# byteworker.net
KiCad netlist of a schematic drawn in EAGLE
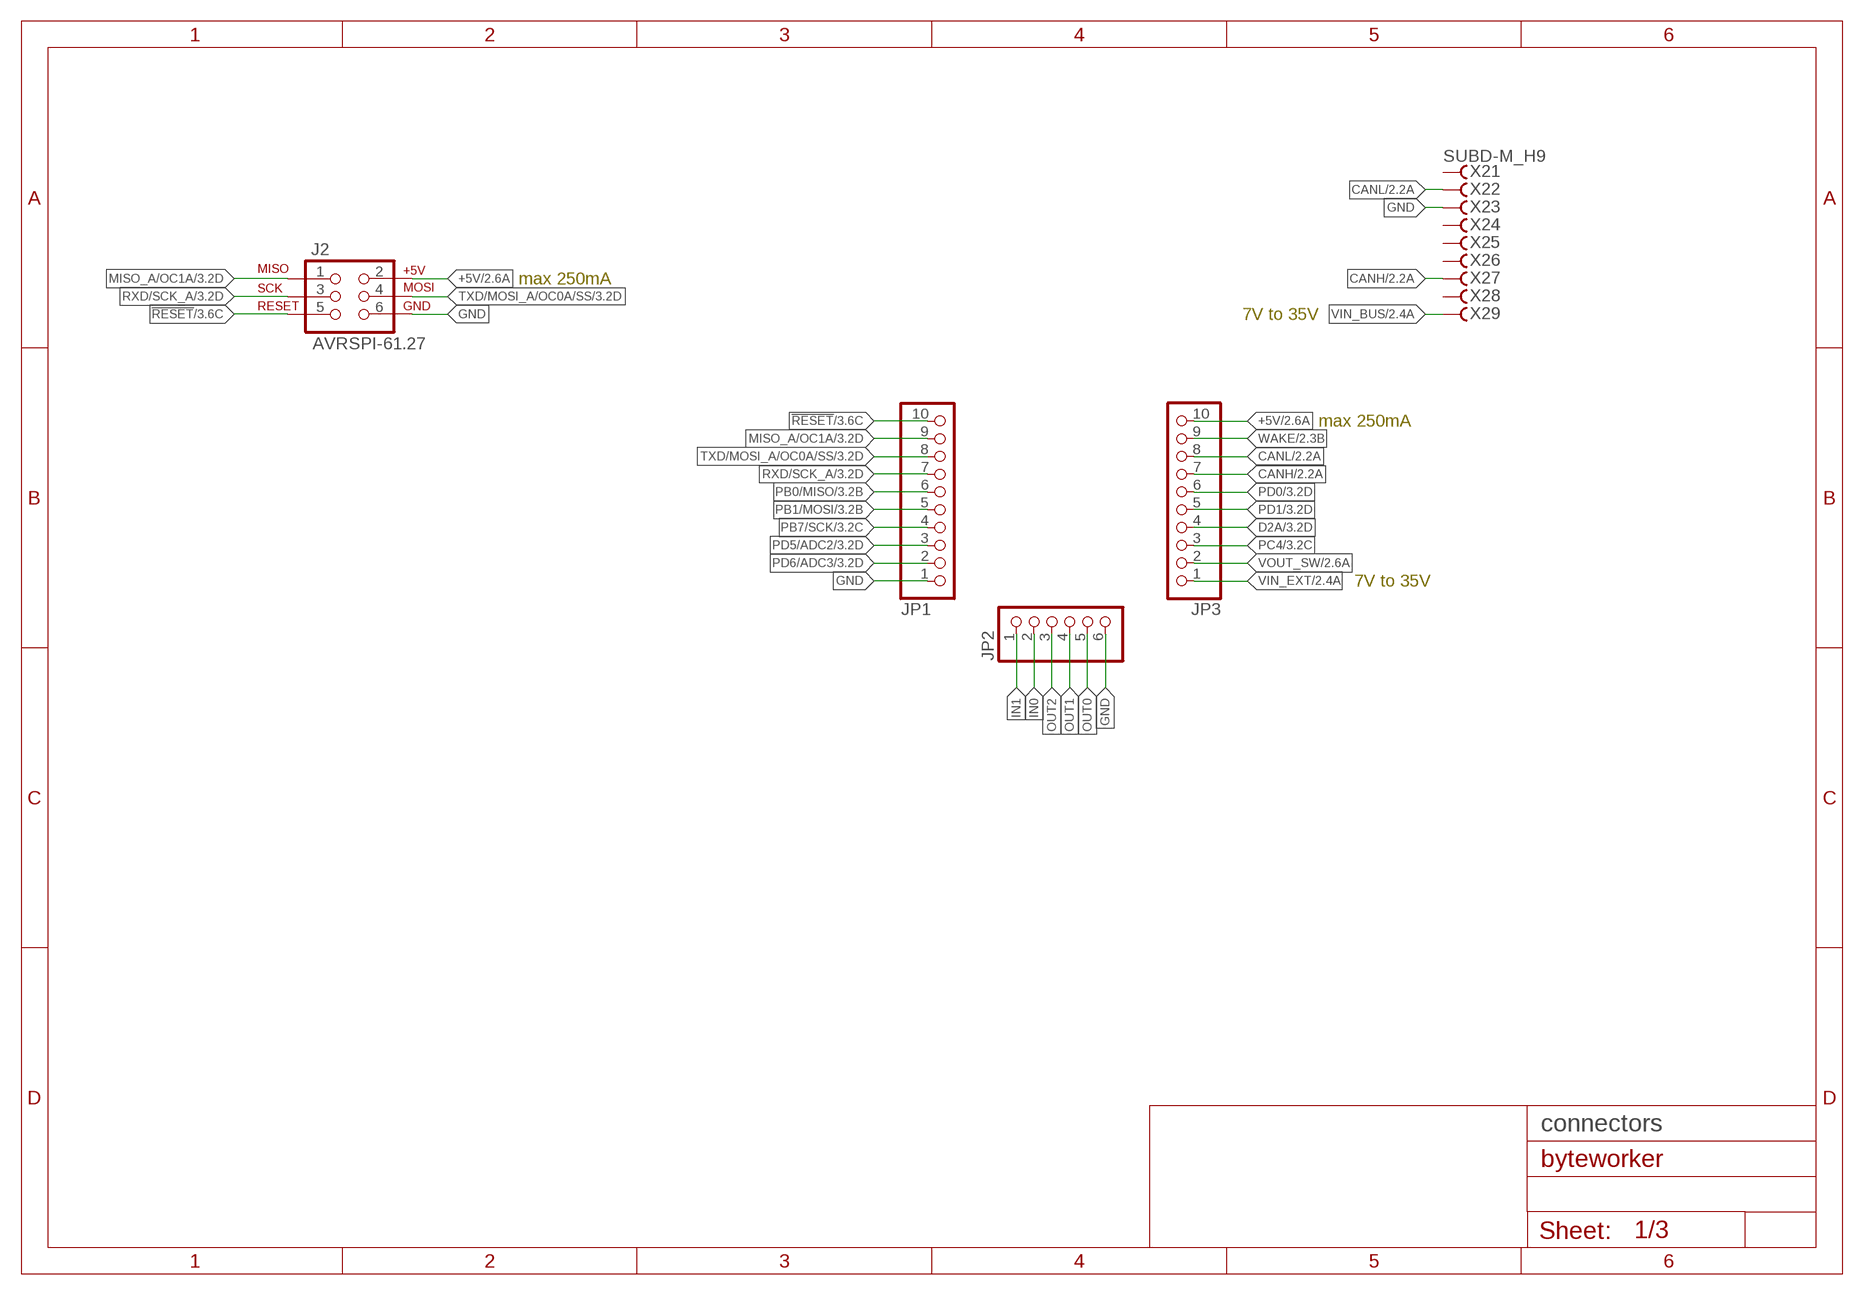
[diagram p0: schematic, sheet 1]
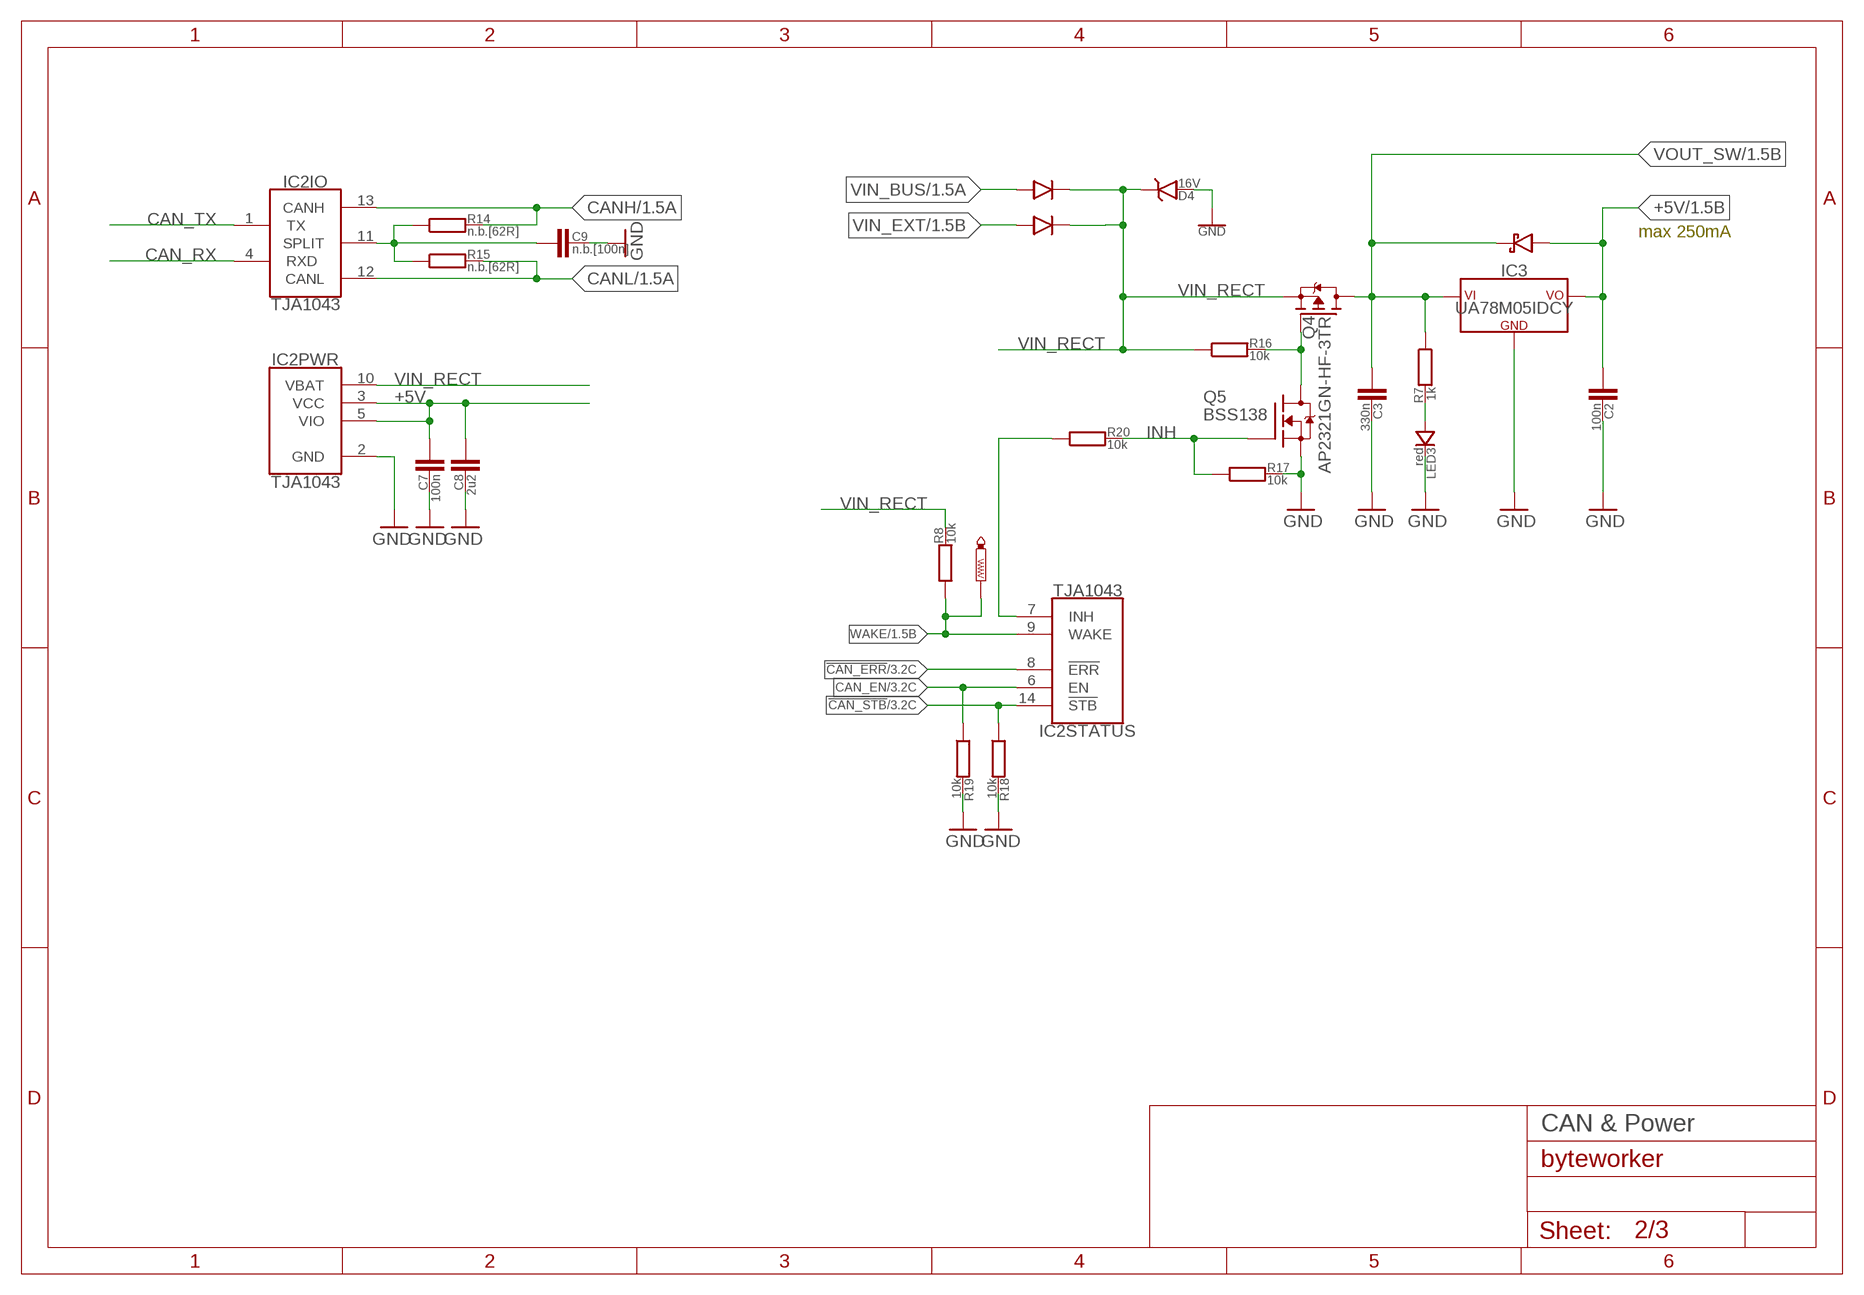
[diagram p1: schematic, sheet 2]
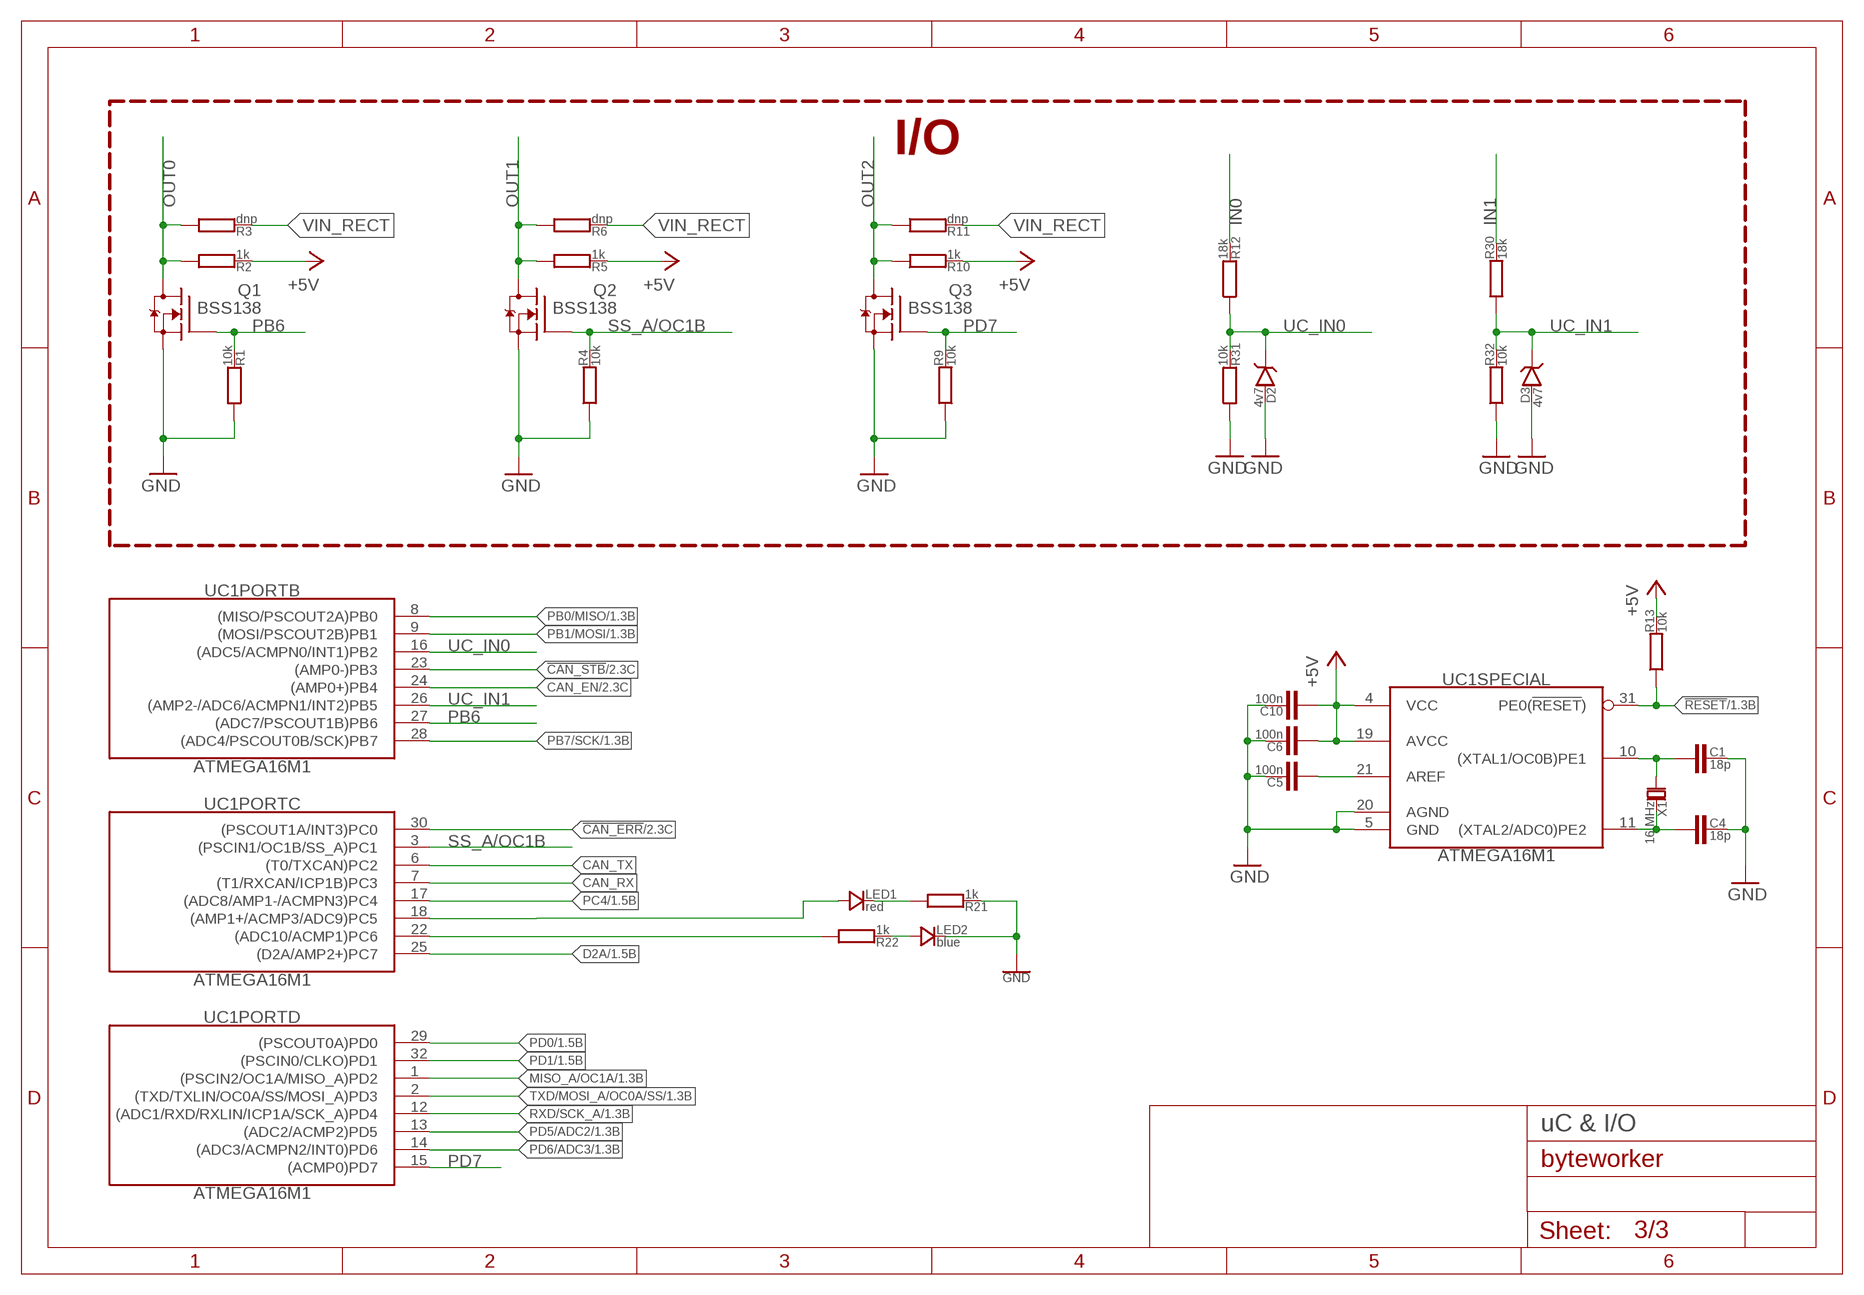
[diagram p2: schematic, sheet 3]

(export (version "E")
  (design (tool "Eeschema 10.0.6"))
  (components
    (comp (ref "C2")
      (value "100n")
      (footprint "eagle-import:C0603")
      (libsource (lib "eagle-import") (part "C0603"))
    )
    (comp (ref "C3")
      (value "330n")
      (footprint "eagle-import:C0603")
      (libsource (lib "eagle-import") (part "C0603"))
    )
    (comp (ref "C7")
      (value "100n")
      (footprint "eagle-import:C0603")
      (libsource (lib "eagle-import") (part "C0603"))
    )
    (comp (ref "C8")
      (value "2u2")
      (footprint "eagle-import:C0805")
      (libsource (lib "eagle-import") (part "C0805"))
    )
    (comp (ref "C9")
      (value "n.b.[100n]")
      (footprint "eagle-import:C0603")
      (libsource (lib "eagle-import") (part "C0603"))
    )
    (comp (ref "D1")
      (value "1N5819HW")
      (footprint "eagle-import:SOD123")
      (libsource (lib "eagle-import") (part "1N5819HW"))
    )
    (comp (ref "D4")
      (value "16V")
      (footprint "eagle-import:SOD-128")
      (fields (field (name "MF") "NXP") (field (name "MPN") "PTVS18VP1UP"))
      (libsource (lib "eagle-import") (part "ZENER_PTVS18VP1UP"))
    )
    (comp (ref "D5")
      (value "1N5819HW")
      (footprint "eagle-import:SOD123")
      (libsource (lib "eagle-import") (part "1N5819HW"))
    )
    (comp (ref "D6")
      (value "SCHOTTKY323")
      (footprint "eagle-import:SOD323")
      (libsource (lib "eagle-import") (part "SCHOTTKY323"))
    )
    (comp (ref "IC2")
      (value "TJA1043")
      (footprint "eagle-import:SO14")
      (fields (field (name "MF") "NXP") (field (name "MPN") "TJA1043T,118"))
      (libsource (lib "eagle-import") (part "TJA1043"))
    )
    (comp (ref "IC3")
      (value "UA78M05IDCY")
      (footprint "eagle-import:SOT223")
      (fields (field (name "MF") "TEXAS INSTRUMENTS"))
      (libsource (lib "eagle-import") (part "UA78M05IDCY"))
    )
    (comp (ref "LED3")
      (value "red")
      (footprint "eagle-import:LED0603")
      (libsource (lib "eagle-import") (part "LED0603"))
    )
    (comp (ref "Q4")
      (value "AP2321GN-HF-3TR")
      (footprint "eagle-import:SOT23-3")
      (fields (field (name "MF") " ADVANCED POWER ELECTRONICS CORP"))
      (libsource (lib "eagle-import") (part "AP2321GN-HF-3TR"))
    )
    (comp (ref "Q5")
      (value "BSS138")
      (footprint "eagle-import:SOT23C")
      (fields (field (name "MF") "   Fairchild Semiconductor"))
      (libsource (lib "eagle-import") (part "BSS138"))
    )
    (comp (ref "R7")
      (value "1k")
      (footprint "eagle-import:R0603")
      (libsource (lib "eagle-import") (part "R0603"))
    )
    (comp (ref "R8")
      (value "10k")
      (footprint "eagle-import:R0603")
      (libsource (lib "eagle-import") (part "R0603"))
    )
    (comp (ref "R14")
      (value "n.b.[62R]")
      (footprint "eagle-import:R0603")
      (libsource (lib "eagle-import") (part "R0603"))
    )
    (comp (ref "R15")
      (value "n.b.[62R]")
      (footprint "eagle-import:R0603")
      (libsource (lib "eagle-import") (part "R0603"))
    )
    (comp (ref "R16")
      (value "10k")
      (footprint "eagle-import:R0603")
      (libsource (lib "eagle-import") (part "R0603"))
    )
    (comp (ref "R17")
      (value "10k")
      (footprint "eagle-import:R0603")
      (libsource (lib "eagle-import") (part "R0603"))
    )
    (comp (ref "R18")
      (value "10k")
      (footprint "eagle-import:R0603")
      (libsource (lib "eagle-import") (part "R0603"))
    )
    (comp (ref "R19")
      (value "10k")
      (footprint "eagle-import:R0603")
      (libsource (lib "eagle-import") (part "R0603"))
    )
    (comp (ref "R20")
      (value "10k")
      (footprint "eagle-import:R0603")
      (libsource (lib "eagle-import") (part "R0603"))
    )
    (comp (ref "TP2")
      (value "PTR1B1,27")
      (footprint "eagle-import:B1,27")
      (libsource (lib "eagle-import") (part "PTR1B1,27"))
    )
    (comp (ref "C1")
      (value "18p")
      (footprint "eagle-import:C0603")
      (libsource (lib "eagle-import") (part "C0603"))
    )
    (comp (ref "C4")
      (value "18p")
      (footprint "eagle-import:C0603")
      (libsource (lib "eagle-import") (part "C0603"))
    )
    (comp (ref "C5")
      (value "100n")
      (footprint "eagle-import:C0603")
      (libsource (lib "eagle-import") (part "C0603"))
    )
    (comp (ref "C6")
      (value "100n")
      (footprint "eagle-import:C0603")
      (libsource (lib "eagle-import") (part "C0603"))
    )
    (comp (ref "C10")
      (value "100n")
      (footprint "eagle-import:C0603")
      (libsource (lib "eagle-import") (part "C0603"))
    )
    (comp (ref "D2")
      (value "4v7")
      (footprint "eagle-import:SOD80")
      (libsource (lib "eagle-import") (part "bytewerk-passive_ZENER"))
    )
    (comp (ref "D3")
      (value "4v7")
      (footprint "eagle-import:SOD80")
      (libsource (lib "eagle-import") (part "bytewerk-passive_ZENER"))
    )
    (comp (ref "LED1")
      (value "red")
      (footprint "eagle-import:LED0603")
      (libsource (lib "eagle-import") (part "LED0603"))
    )
    (comp (ref "LED2")
      (value "blue")
      (footprint "eagle-import:LED0603")
      (libsource (lib "eagle-import") (part "LED0603"))
    )
    (comp (ref "Q1")
      (value "BSS138")
      (footprint "eagle-import:SOT23C")
      (fields (field (name "MF") "   Fairchild Semiconductor"))
      (libsource (lib "eagle-import") (part "BSS138"))
    )
    (comp (ref "Q2")
      (value "BSS138")
      (footprint "eagle-import:SOT23C")
      (fields (field (name "MF") "   Fairchild Semiconductor"))
      (libsource (lib "eagle-import") (part "BSS138"))
    )
    (comp (ref "Q3")
      (value "BSS138")
      (footprint "eagle-import:SOT23C")
      (fields (field (name "MF") "   Fairchild Semiconductor"))
      (libsource (lib "eagle-import") (part "BSS138"))
    )
    (comp (ref "R1")
      (value "10k")
      (footprint "eagle-import:R0603")
      (libsource (lib "eagle-import") (part "bytewerk-rcl_R0603"))
    )
    (comp (ref "R2")
      (value "1k")
      (footprint "eagle-import:R0603")
      (libsource (lib "eagle-import") (part "bytewerk-rcl_R0603"))
    )
    (comp (ref "R3")
      (value "dnp")
      (footprint "eagle-import:R0603")
      (libsource (lib "eagle-import") (part "bytewerk-rcl_R0603"))
    )
    (comp (ref "R4")
      (value "10k")
      (footprint "eagle-import:R0603")
      (libsource (lib "eagle-import") (part "bytewerk-rcl_R0603"))
    )
    (comp (ref "R5")
      (value "1k")
      (footprint "eagle-import:R0603")
      (libsource (lib "eagle-import") (part "bytewerk-rcl_R0603"))
    )
    (comp (ref "R6")
      (value "dnp")
      (footprint "eagle-import:R0603")
      (libsource (lib "eagle-import") (part "bytewerk-rcl_R0603"))
    )
    (comp (ref "R9")
      (value "10k")
      (footprint "eagle-import:R0603")
      (libsource (lib "eagle-import") (part "bytewerk-rcl_R0603"))
    )
    (comp (ref "R10")
      (value "1k")
      (footprint "eagle-import:R0603")
      (libsource (lib "eagle-import") (part "bytewerk-rcl_R0603"))
    )
    (comp (ref "R11")
      (value "dnp")
      (footprint "eagle-import:R0603")
      (libsource (lib "eagle-import") (part "bytewerk-rcl_R0603"))
    )
    (comp (ref "R12")
      (value "18k")
      (footprint "eagle-import:R0603")
      (libsource (lib "eagle-import") (part "bytewerk-rcl_R0603"))
    )
    (comp (ref "R13")
      (value "10k")
      (footprint "eagle-import:R0603")
      (libsource (lib "eagle-import") (part "R0603"))
    )
    (comp (ref "R21")
      (value "1k")
      (footprint "eagle-import:R0603")
      (libsource (lib "eagle-import") (part "R0603"))
    )
    (comp (ref "R22")
      (value "1k")
      (footprint "eagle-import:R0603")
      (libsource (lib "eagle-import") (part "R0603"))
    )
    (comp (ref "R30")
      (value "18k")
      (footprint "eagle-import:R0603")
      (libsource (lib "eagle-import") (part "bytewerk-rcl_R0603"))
    )
    (comp (ref "R31")
      (value "10k")
      (footprint "eagle-import:R0603")
      (libsource (lib "eagle-import") (part "bytewerk-rcl_R0603"))
    )
    (comp (ref "R32")
      (value "10k")
      (footprint "eagle-import:R0603")
      (libsource (lib "eagle-import") (part "bytewerk-rcl_R0603"))
    )
    (comp (ref "UC1")
      (value "ATMEGA16M1")
      (footprint "eagle-import:TQFP32-08")
      (libsource (lib "eagle-import") (part "ATMEGA16M1"))
    )
    (comp (ref "X1")
      (value "16 MHz")
      (footprint "eagle-import:5.0X3.2")
      (libsource (lib "eagle-import") (part "CRYSTAL5X3.2"))
    )
    (comp (ref "J2")
      (value "AVRSPI-61.27")
      (footprint "eagle-import:2X3-1.27")
      (libsource (lib "eagle-import") (part "AVRSPI-61.27"))
    )
    (comp (ref "JP1")
      (value "PINHD-1X10")
      (footprint "eagle-import:1X10")
      (libsource (lib "eagle-import") (part "PINHD-1X10"))
    )
    (comp (ref "JP2")
      (value "PINHD-1X6")
      (footprint "eagle-import:1X06")
      (libsource (lib "eagle-import") (part "PINHD-1X6"))
    )
    (comp (ref "JP3")
      (value "PINHD-1X10")
      (footprint "eagle-import:1X10")
      (libsource (lib "eagle-import") (part "PINHD-1X10"))
    )
    (comp (ref "X2")
      (value "SUBD-M_H9")
      (footprint "eagle-import:SUBD9")
      (libsource (lib "eagle-import") (part "SUBD-M_H9"))
    )
  )
  (nets
    (net (code "1") (name "+5V") (class "Default")
      (node (ref "C10") (pin "1") (pinfunction "1_1") (pintype "passive"))
      (node (ref "C2") (pin "1") (pinfunction "1_1") (pintype "passive"))
      (node (ref "C6") (pin "1") (pinfunction "1_1") (pintype "passive"))
      (node (ref "C7") (pin "1") (pinfunction "1_1") (pintype "passive"))
      (node (ref "C8") (pin "1") (pinfunction "1_1") (pintype "passive"))
      (node (ref "D6") (pin "A") (pinfunction "A_A") (pintype "passive"))
      (node (ref "IC2") (pin "3") (pinfunction "VCC_3") (pintype "power_in"))
      (node (ref "IC2") (pin "5") (pinfunction "VIO_5") (pintype "power_in"))
      (node (ref "IC3") (pin "3") (pinfunction "+5V_3") (pintype "power_in"))
      (node (ref "J2") (pin "2") (pinfunction "+5V_2") (pintype "passive"))
      (node (ref "JP3") (pin "10") (pinfunction "10_10") (pintype "passive"))
      (node (ref "R10") (pin "2") (pinfunction "2_2") (pintype "passive"))
      (node (ref "R13") (pin "2") (pinfunction "2_2") (pintype "passive"))
      (node (ref "R2") (pin "2") (pinfunction "2_2") (pintype "passive"))
      (node (ref "R5") (pin "2") (pinfunction "2_2") (pintype "passive"))
      (node (ref "UC1") (pin "19") (pinfunction "AVCC_19") (pintype "power_in"))
      (node (ref "UC1") (pin "4") (pinfunction "VCC_4") (pintype "power_in"))
    )
    (net (code "2") (name "CANH") (class "Default")
      (node (ref "IC2") (pin "13") (pinfunction "CANH_13") (pintype "passive"))
      (node (ref "JP3") (pin "7") (pinfunction "7_7") (pintype "passive"))
      (node (ref "R14") (pin "2") (pinfunction "2_2") (pintype "passive"))
      (node (ref "X2") (pin "8") (pinfunction "F_8") (pintype "passive"))
    )
    (net (code "3") (name "CANL") (class "Default")
      (node (ref "IC2") (pin "12") (pinfunction "CANL_12") (pintype "passive"))
      (node (ref "JP3") (pin "8") (pinfunction "8_8") (pintype "passive"))
      (node (ref "R15") (pin "2") (pinfunction "2_2") (pintype "passive"))
      (node (ref "X2") (pin "4") (pinfunction "F_4") (pintype "passive"))
    )
    (net (code "4") (name "CAN_EN") (class "Default")
      (node (ref "IC2") (pin "6") (pinfunction "EN_6") (pintype "input"))
      (node (ref "R19") (pin "1") (pinfunction "1_1") (pintype "passive"))
      (node (ref "UC1") (pin "24") (pinfunction "(AMP0+)PB4_24") (pintype "bidirectional"))
    )
    (net (code "5") (name "CAN_RX") (class "Default")
      (node (ref "IC2") (pin "4") (pinfunction "RXD_4") (pintype "output"))
      (node (ref "UC1") (pin "7") (pinfunction "(T1/RXCAN/ICP1B)PC3_7") (pintype "bidirectional"))
    )
    (net (code "6") (name "CAN_TX") (class "Default")
      (node (ref "IC2") (pin "1") (pinfunction "TX_1") (pintype "input"))
      (node (ref "UC1") (pin "6") (pinfunction "(T0/TXCAN)PC2_6") (pintype "bidirectional"))
    )
    (net (code "7") (name "D2A") (class "Default")
      (node (ref "JP3") (pin "4") (pinfunction "4_4") (pintype "passive"))
      (node (ref "UC1") (pin "25") (pinfunction "(D2A/AMP2+)PC7_25") (pintype "bidirectional"))
    )
    (net (code "8") (name "GND") (class "Default")
      (node (ref "C1") (pin "2") (pinfunction "2_2") (pintype "passive"))
      (node (ref "C10") (pin "2") (pinfunction "2_2") (pintype "passive"))
      (node (ref "C2") (pin "2") (pinfunction "2_2") (pintype "passive"))
      (node (ref "C3") (pin "2") (pinfunction "2_2") (pintype "passive"))
      (node (ref "C4") (pin "2") (pinfunction "2_2") (pintype "passive"))
      (node (ref "C5") (pin "2") (pinfunction "2_2") (pintype "passive"))
      (node (ref "C6") (pin "2") (pinfunction "2_2") (pintype "passive"))
      (node (ref "C7") (pin "2") (pinfunction "2_2") (pintype "passive"))
      (node (ref "C8") (pin "2") (pinfunction "2_2") (pintype "passive"))
      (node (ref "C9") (pin "2") (pinfunction "2_2") (pintype "passive"))
      (node (ref "D2") (pin "A") (pinfunction "A_A") (pintype "passive"))
      (node (ref "D3") (pin "A") (pinfunction "A_A") (pintype "passive"))
      (node (ref "D4") (pin "A") (pinfunction "A_A") (pintype "passive"))
      (node (ref "IC2") (pin "2") (pinfunction "GND_2") (pintype "power_in"))
      (node (ref "IC3") (pin "2") (pinfunction "GND_2") (pintype "power_in"))
      (node (ref "IC3") (pin "4") (pinfunction "GND_4") (pintype "power_in"))
      (node (ref "J2") (pin "6") (pinfunction "GND_6") (pintype "passive"))
      (node (ref "JP1") (pin "1") (pinfunction "1_1") (pintype "passive"))
      (node (ref "JP2") (pin "6") (pinfunction "6_6") (pintype "passive"))
      (node (ref "LED2") (pin "C") (pinfunction "C_C") (pintype "passive"))
      (node (ref "LED3") (pin "C") (pinfunction "C_C") (pintype "passive"))
      (node (ref "Q1") (pin "2") (pinfunction "S_2") (pintype "passive"))
      (node (ref "Q2") (pin "2") (pinfunction "S_2") (pintype "passive"))
      (node (ref "Q3") (pin "2") (pinfunction "S_2") (pintype "passive"))
      (node (ref "Q5") (pin "2") (pinfunction "S_2") (pintype "passive"))
      (node (ref "R1") (pin "1") (pinfunction "1_1") (pintype "passive"))
      (node (ref "R17") (pin "2") (pinfunction "2_2") (pintype "passive"))
      (node (ref "R18") (pin "2") (pinfunction "2_2") (pintype "passive"))
      (node (ref "R19") (pin "2") (pinfunction "2_2") (pintype "passive"))
      (node (ref "R21") (pin "2") (pinfunction "2_2") (pintype "passive"))
      (node (ref "R31") (pin "1") (pinfunction "1_1") (pintype "passive"))
      (node (ref "R32") (pin "1") (pinfunction "1_1") (pintype "passive"))
      (node (ref "R4") (pin "1") (pinfunction "1_1") (pintype "passive"))
      (node (ref "R9") (pin "1") (pinfunction "1_1") (pintype "passive"))
      (node (ref "UC1") (pin "20") (pinfunction "AGND_20") (pintype "power_in"))
      (node (ref "UC1") (pin "5") (pinfunction "GND_5") (pintype "power_in"))
      (node (ref "X2") (pin "3") (pinfunction "F_3") (pintype "passive"))
    )
    (net (code "9") (name "IN0") (class "Default")
      (node (ref "JP2") (pin "2") (pinfunction "2_2") (pintype "passive"))
      (node (ref "R12") (pin "2") (pinfunction "2_2") (pintype "passive"))
    )
    (net (code "10") (name "IN1") (class "Default")
      (node (ref "JP2") (pin "1") (pinfunction "1_1") (pintype "passive"))
      (node (ref "R30") (pin "2") (pinfunction "2_2") (pintype "passive"))
    )
    (net (code "11") (name "INH") (class "Default")
      (node (ref "Q5") (pin "1") (pinfunction "G_1") (pintype "passive"))
      (node (ref "R17") (pin "1") (pinfunction "1_1") (pintype "passive"))
      (node (ref "R20") (pin "2") (pinfunction "2_2") (pintype "passive"))
    )
    (net (code "12") (name "MISO_A{slash}OC1A") (class "Default")
      (node (ref "J2") (pin "1") (pinfunction "MISO_1") (pintype "passive"))
      (node (ref "JP1") (pin "9") (pinfunction "9_9") (pintype "passive"))
      (node (ref "UC1") (pin "1") (pinfunction "(PSCIN2/OC1A/MISO_A)PD2_1") (pintype "bidirectional"))
    )
    (net (code "13") (name "Net-(IC2A-SPLIT)") (class "Default")
      (node (ref "C9") (pin "1") (pinfunction "1_1") (pintype "passive"))
      (node (ref "IC2") (pin "11") (pinfunction "SPLIT_11") (pintype "passive"))
      (node (ref "R14") (pin "1") (pinfunction "1_1") (pintype "passive"))
      (node (ref "R15") (pin "1") (pinfunction "1_1") (pintype "passive"))
    )
    (net (code "14") (name "Net-(IC2C-INH)") (class "Default")
      (node (ref "IC2") (pin "7") (pinfunction "INH_7") (pintype "output"))
      (node (ref "R20") (pin "1") (pinfunction "1_1") (pintype "passive"))
    )
    (net (code "15") (name "Net-(LED1-PadC)") (class "Default")
      (node (ref "LED1") (pin "C") (pinfunction "C_C") (pintype "passive"))
      (node (ref "R21") (pin "1") (pinfunction "1_1") (pintype "passive"))
    )
    (net (code "16") (name "Net-(LED2-PadA)") (class "Default")
      (node (ref "LED2") (pin "A") (pinfunction "A_A") (pintype "passive"))
      (node (ref "R22") (pin "2") (pinfunction "2_2") (pintype "passive"))
    )
    (net (code "17") (name "Net-(LED3-PadA)") (class "Default")
      (node (ref "LED3") (pin "A") (pinfunction "A_A") (pintype "passive"))
      (node (ref "R7") (pin "2") (pinfunction "2_2") (pintype "passive"))
    )
    (net (code "18") (name "Net-(Q4-G)") (class "Default")
      (node (ref "Q4") (pin "1") (pinfunction "G_1") (pintype "passive"))
      (node (ref "Q5") (pin "3") (pinfunction "D_3") (pintype "passive"))
      (node (ref "R16") (pin "2") (pinfunction "2_2") (pintype "passive"))
    )
    (net (code "19") (name "Net-(UC1B-(ADC10{slash}ACMP1)PC6)") (class "Default")
      (node (ref "R22") (pin "1") (pinfunction "1_1") (pintype "passive"))
      (node (ref "UC1") (pin "22") (pinfunction "(ADC10/ACMP1)PC6_22") (pintype "bidirectional"))
    )
    (net (code "20") (name "Net-(UC1B-(AMP1+{slash}ACMP3{slash}ADC9)PC5)") (class "Default")
      (node (ref "LED1") (pin "A") (pinfunction "A_A") (pintype "passive"))
      (node (ref "UC1") (pin "18") (pinfunction "(AMP1+/ACMP3/ADC9)PC5_18") (pintype "bidirectional"))
    )
    (net (code "21") (name "Net-(UC1D-(XTAL1{slash}OC0B)PE1)") (class "Default")
      (node (ref "C1") (pin "1") (pinfunction "1_1") (pintype "passive"))
      (node (ref "UC1") (pin "10") (pinfunction "(XTAL1/OC0B)PE1_10") (pintype "passive"))
      (node (ref "X1") (pin "1") (pinfunction "1_1") (pintype "passive"))
    )
    (net (code "22") (name "Net-(UC1D-(XTAL2{slash}ADC0)PE2)") (class "Default")
      (node (ref "C4") (pin "1") (pinfunction "1_1") (pintype "passive"))
      (node (ref "UC1") (pin "11") (pinfunction "(XTAL2/ADC0)PE2_11") (pintype "passive"))
      (node (ref "X1") (pin "2") (pinfunction "2_2") (pintype "passive"))
    )
    (net (code "23") (name "Net-(UC1D-AREF)") (class "Default")
      (node (ref "C5") (pin "1") (pinfunction "1_1") (pintype "passive"))
      (node (ref "UC1") (pin "21") (pinfunction "AREF_21") (pintype "passive"))
    )
    (net (code "24") (name "OUT0") (class "Default")
      (node (ref "JP2") (pin "5") (pinfunction "5_5") (pintype "passive"))
      (node (ref "Q1") (pin "3") (pinfunction "D_3") (pintype "passive"))
      (node (ref "R2") (pin "1") (pinfunction "1_1") (pintype "passive"))
      (node (ref "R3") (pin "1") (pinfunction "1_1") (pintype "passive"))
    )
    (net (code "25") (name "OUT1") (class "Default")
      (node (ref "JP2") (pin "4") (pinfunction "4_4") (pintype "passive"))
      (node (ref "Q2") (pin "3") (pinfunction "D_3") (pintype "passive"))
      (node (ref "R5") (pin "1") (pinfunction "1_1") (pintype "passive"))
      (node (ref "R6") (pin "1") (pinfunction "1_1") (pintype "passive"))
    )
    (net (code "26") (name "OUT2") (class "Default")
      (node (ref "JP2") (pin "3") (pinfunction "3_3") (pintype "passive"))
      (node (ref "Q3") (pin "3") (pinfunction "D_3") (pintype "passive"))
      (node (ref "R10") (pin "1") (pinfunction "1_1") (pintype "passive"))
      (node (ref "R11") (pin "1") (pinfunction "1_1") (pintype "passive"))
    )
    (net (code "27") (name "PB0{slash}MISO") (class "Default")
      (node (ref "JP1") (pin "6") (pinfunction "6_6") (pintype "passive"))
      (node (ref "UC1") (pin "8") (pinfunction "(MISO/PSCOUT2A)PB0_8") (pintype "bidirectional"))
    )
    (net (code "28") (name "PB1{slash}MOSI") (class "Default")
      (node (ref "JP1") (pin "5") (pinfunction "5_5") (pintype "passive"))
      (node (ref "UC1") (pin "9") (pinfunction "(MOSI/PSCOUT2B)PB1_9") (pintype "bidirectional"))
    )
    (net (code "29") (name "PB6") (class "Default")
      (node (ref "Q1") (pin "1") (pinfunction "G_1") (pintype "passive"))
      (node (ref "R1") (pin "2") (pinfunction "2_2") (pintype "passive"))
      (node (ref "UC1") (pin "27") (pinfunction "(ADC7/PSCOUT1B)PB6_27") (pintype "bidirectional"))
    )
    (net (code "30") (name "PB7{slash}SCK") (class "Default")
      (node (ref "JP1") (pin "4") (pinfunction "4_4") (pintype "passive"))
      (node (ref "UC1") (pin "28") (pinfunction "(ADC4/PSCOUT0B/SCK)PB7_28") (pintype "bidirectional"))
    )
    (net (code "31") (name "PC4") (class "Default")
      (node (ref "JP3") (pin "3") (pinfunction "3_3") (pintype "passive"))
      (node (ref "UC1") (pin "17") (pinfunction "(ADC8/AMP1-/ACMPN3)PC4_17") (pintype "bidirectional"))
    )
    (net (code "32") (name "PD0") (class "Default")
      (node (ref "JP3") (pin "6") (pinfunction "6_6") (pintype "passive"))
      (node (ref "UC1") (pin "29") (pinfunction "(PSCOUT0A)PD0_29") (pintype "bidirectional"))
    )
    (net (code "33") (name "PD1") (class "Default")
      (node (ref "JP3") (pin "5") (pinfunction "5_5") (pintype "passive"))
      (node (ref "UC1") (pin "32") (pinfunction "(PSCIN0/CLKO)PD1_32") (pintype "bidirectional"))
    )
    (net (code "34") (name "PD5{slash}ADC2") (class "Default")
      (node (ref "JP1") (pin "3") (pinfunction "3_3") (pintype "passive"))
      (node (ref "UC1") (pin "13") (pinfunction "(ADC2/ACMP2)PD5_13") (pintype "bidirectional"))
    )
    (net (code "35") (name "PD6{slash}ADC3") (class "Default")
      (node (ref "JP1") (pin "2") (pinfunction "2_2") (pintype "passive"))
      (node (ref "UC1") (pin "14") (pinfunction "(ADC3/ACMPN2/INT0)PD6_14") (pintype "bidirectional"))
    )
    (net (code "36") (name "PD7") (class "Default")
      (node (ref "Q3") (pin "1") (pinfunction "G_1") (pintype "passive"))
      (node (ref "R9") (pin "2") (pinfunction "2_2") (pintype "passive"))
      (node (ref "UC1") (pin "15") (pinfunction "(ACMP0)PD7_15") (pintype "bidirectional"))
    )
    (net (code "37") (name "RXD{slash}SCK_A") (class "Default")
      (node (ref "J2") (pin "3") (pinfunction "SCK_3") (pintype "passive"))
      (node (ref "JP1") (pin "7") (pinfunction "7_7") (pintype "passive"))
      (node (ref "UC1") (pin "12") (pinfunction "(ADC1/RXD/RXLIN/ICP1A/SCK_A)PD4_12") (pintype "bidirectional"))
    )
    (net (code "38") (name "SS_A{slash}OC1B") (class "Default")
      (node (ref "Q2") (pin "1") (pinfunction "G_1") (pintype "passive"))
      (node (ref "R4") (pin "2") (pinfunction "2_2") (pintype "passive"))
      (node (ref "UC1") (pin "3") (pinfunction "(PSCIN1/OC1B/SS_A)PC1_3") (pintype "bidirectional"))
    )
    (net (code "39") (name "TXD{slash}MOSI_A{slash}OC0A{slash}SS") (class "Default")
      (node (ref "J2") (pin "4") (pinfunction "MOSI_4") (pintype "passive"))
      (node (ref "JP1") (pin "8") (pinfunction "8_8") (pintype "passive"))
      (node (ref "UC1") (pin "2") (pinfunction "(TXD/TXLIN/OC0A/SS/MOSI_A)PD3_2") (pintype "bidirectional"))
    )
    (net (code "40") (name "UC_IN0") (class "Default")
      (node (ref "D2") (pin "C") (pinfunction "C_C") (pintype "passive"))
      (node (ref "R12") (pin "1") (pinfunction "1_1") (pintype "passive"))
      (node (ref "R31") (pin "2") (pinfunction "2_2") (pintype "passive"))
      (node (ref "UC1") (pin "16") (pinfunction "(ADC5/ACMPN0/INT1)PB2_16") (pintype "bidirectional"))
    )
    (net (code "41") (name "UC_IN1") (class "Default")
      (node (ref "D3") (pin "C") (pinfunction "C_C") (pintype "passive"))
      (node (ref "R30") (pin "1") (pinfunction "1_1") (pintype "passive"))
      (node (ref "R32") (pin "2") (pinfunction "2_2") (pintype "passive"))
      (node (ref "UC1") (pin "26") (pinfunction "(AMP2-/ADC6/ACMPN1/INT2)PB5_26") (pintype "bidirectional"))
    )
    (net (code "42") (name "VIN_BUS") (class "Default")
      (node (ref "D5") (pin "A") (pinfunction "A_A") (pintype "passive"))
      (node (ref "X2") (pin "6") (pinfunction "F_6") (pintype "passive"))
    )
    (net (code "43") (name "VIN_EXT") (class "Default")
      (node (ref "D1") (pin "A") (pinfunction "A_A") (pintype "passive"))
      (node (ref "JP3") (pin "1") (pinfunction "1_1") (pintype "passive"))
    )
    (net (code "44") (name "VIN_RECT") (class "Default")
      (node (ref "D1") (pin "C") (pinfunction "C_C") (pintype "passive"))
      (node (ref "D4") (pin "C") (pinfunction "C_C") (pintype "passive"))
      (node (ref "D5") (pin "C") (pinfunction "C_C") (pintype "passive"))
      (node (ref "IC2") (pin "10") (pinfunction "VBAT_10") (pintype "power_in"))
      (node (ref "Q4") (pin "2") (pinfunction "S_2") (pintype "passive"))
      (node (ref "R11") (pin "2") (pinfunction "2_2") (pintype "passive"))
      (node (ref "R16") (pin "1") (pinfunction "1_1") (pintype "passive"))
      (node (ref "R3") (pin "2") (pinfunction "2_2") (pintype "passive"))
      (node (ref "R6") (pin "2") (pinfunction "2_2") (pintype "passive"))
      (node (ref "R8") (pin "2") (pinfunction "2_2") (pintype "passive"))
    )
    (net (code "45") (name "VOUT_SW") (class "Default")
      (node (ref "C3") (pin "1") (pinfunction "1_1") (pintype "passive"))
      (node (ref "D6") (pin "C") (pinfunction "C_C") (pintype "passive"))
      (node (ref "IC3") (pin "1") (pinfunction "VIN_1") (pintype "power_in"))
      (node (ref "JP3") (pin "2") (pinfunction "2_2") (pintype "passive"))
      (node (ref "Q4") (pin "3") (pinfunction "D_3") (pintype "passive"))
      (node (ref "R7") (pin "1") (pinfunction "1_1") (pintype "passive"))
    )
    (net (code "46") (name "WAKE") (class "Default")
      (node (ref "IC2") (pin "9") (pinfunction "WAKE_9") (pintype "input"))
      (node (ref "JP3") (pin "9") (pinfunction "9_9") (pintype "passive"))
      (node (ref "R8") (pin "1") (pinfunction "1_1") (pintype "passive"))
      (node (ref "TP2") (pin "TP") (pinfunction "TP_TP") (pintype "input"))
    )
    (net (code "47") (name "unconnected-(X2A-F-Pad5)") (class "Default")
      (node (ref "X2") (pin "5") (pinfunction "F_5") (pintype "passive"))
    )
    (net (code "48") (name "unconnected-(X2D-F-Pad2)") (class "Default")
      (node (ref "X2") (pin "2") (pinfunction "F_2") (pintype "passive"))
    )
    (net (code "49") (name "unconnected-(X2E-F-Pad1)") (class "Default")
      (node (ref "X2") (pin "1") (pinfunction "F_1") (pintype "passive"))
    )
    (net (code "50") (name "unconnected-(X2F-F-Pad9)") (class "Default")
      (node (ref "X2") (pin "9") (pinfunction "F_9") (pintype "passive"))
    )
    (net (code "51") (name "unconnected-(X2H-F-Pad7)") (class "Default")
      (node (ref "X2") (pin "7") (pinfunction "F_7") (pintype "passive"))
    )
    (net (code "52") (name "~{CAN_ERR}") (class "Default")
      (node (ref "IC2") (pin "8") (pinfunction "~{ERR}_8") (pintype "output"))
      (node (ref "UC1") (pin "30") (pinfunction "(PSCOUT1A/INT3)PC0_30") (pintype "bidirectional"))
    )
    (net (code "53") (name "~{CAN_STB}") (class "Default")
      (node (ref "IC2") (pin "14") (pinfunction "~{STB}_14") (pintype "input"))
      (node (ref "R18") (pin "1") (pinfunction "1_1") (pintype "passive"))
      (node (ref "UC1") (pin "23") (pinfunction "(AMP0-)PB3_23") (pintype "bidirectional"))
    )
    (net (code "54") (name "~{RESET}") (class "Default")
      (node (ref "J2") (pin "5") (pinfunction "RESET_5") (pintype "passive"))
      (node (ref "JP1") (pin "10") (pinfunction "10_10") (pintype "passive"))
      (node (ref "R13") (pin "1") (pinfunction "1_1") (pintype "passive"))
      (node (ref "UC1") (pin "31") (pinfunction "PE0(~{RESET})_31") (pintype "bidirectional"))
    )
  )
)
